# MODULE_FPGA.net
KiCad netlist of a schematic drawn in Altium Designer
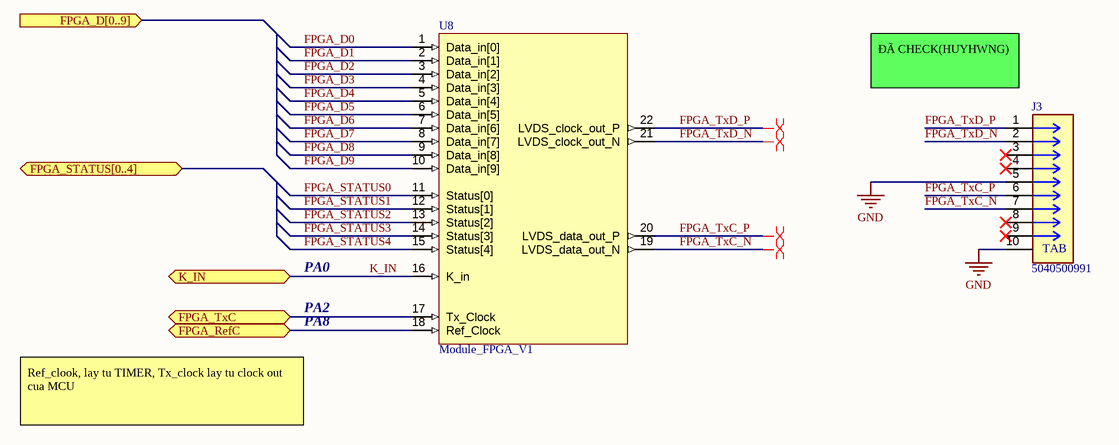
[diagram p0: MODULE_FPGA.SchDoc]

(export (version "E")
  (design (tool "Eeschema 10.0.6"))
  (components
    (comp (ref "J3")
      (value "5040500991")
      (footprint "5040500991")
      (description "Connector Header Surface Mount, Right Angle 9 position 0.059\" (1.50mm)")
      (libsource (lib "COMM_SCHLIB") (part "5040500991"))
    )
    (comp (ref "U8")
      (value "Module_FPGA_V1")
      (footprint "MODULE_FPGA")
      (libsource (lib "3_HuyHung") (part "Module_FPGA_V1"))
    )
  )
  (nets
    (net (code "1") (name "/FPGA_D0") (class "Default")
      (node (ref "U8") (pin "1") (pinfunction "Data_in[0]_1") (pintype "input"))
    )
    (net (code "2") (name "/FPGA_D1") (class "Default")
      (node (ref "U8") (pin "2") (pinfunction "Data_in[1]_2") (pintype "input"))
    )
    (net (code "3") (name "/FPGA_D2") (class "Default")
      (node (ref "U8") (pin "3") (pinfunction "Data_in[2]_3") (pintype "input"))
    )
    (net (code "4") (name "/FPGA_D3") (class "Default")
      (node (ref "U8") (pin "4") (pinfunction "Data_in[3]_4") (pintype "input"))
    )
    (net (code "5") (name "/FPGA_D4") (class "Default")
      (node (ref "U8") (pin "5") (pinfunction "Data_in[4]_5") (pintype "input"))
    )
    (net (code "6") (name "/FPGA_D5") (class "Default")
      (node (ref "U8") (pin "6") (pinfunction "Data_in[5]_6") (pintype "input"))
    )
    (net (code "7") (name "/FPGA_D6") (class "Default")
      (node (ref "U8") (pin "7") (pinfunction "Data_in[6]_7") (pintype "input"))
    )
    (net (code "8") (name "/FPGA_D7") (class "Default")
      (node (ref "U8") (pin "8") (pinfunction "Data_in[7]_8") (pintype "input"))
    )
    (net (code "9") (name "/FPGA_D8") (class "Default")
      (node (ref "U8") (pin "9") (pinfunction "Data_in[8]_9") (pintype "input"))
    )
    (net (code "10") (name "/FPGA_D9") (class "Default")
      (node (ref "U8") (pin "10") (pinfunction "Data_in[9]_10") (pintype "input"))
    )
    (net (code "12") (name "/FPGA_RefC") (class "Default")
      (node (ref "U8") (pin "18") (pinfunction "Ref_Clock_18") (pintype "input"))
    )
    (net (code "13") (name "/FPGA_STATUS0") (class "Default")
      (node (ref "U8") (pin "11") (pinfunction "Status[0]_11") (pintype "input"))
    )
    (net (code "14") (name "/FPGA_STATUS1") (class "Default")
      (node (ref "U8") (pin "12") (pinfunction "Status[1]_12") (pintype "input"))
    )
    (net (code "15") (name "/FPGA_STATUS2") (class "Default")
      (node (ref "U8") (pin "13") (pinfunction "Status[2]_13") (pintype "input"))
    )
    (net (code "16") (name "/FPGA_STATUS3") (class "Default")
      (node (ref "U8") (pin "14") (pinfunction "Status[3]_14") (pintype "input"))
    )
    (net (code "17") (name "/FPGA_STATUS4") (class "Default")
      (node (ref "U8") (pin "15") (pinfunction "Status[4]_15") (pintype "input"))
    )
    (net (code "19") (name "/FPGA_TxC") (class "Default")
      (node (ref "U8") (pin "17") (pinfunction "Tx_Clock_17") (pintype "input"))
    )
    (net (code "20") (name "/FPGA_TxC_N") (class "Default")
      (node (ref "J3") (pin "7") (pinfunction "7_7") (pintype "passive"))
      (node (ref "U8") (pin "19") (pinfunction "LVDS_data_out_N_19") (pintype "output"))
    )
    (net (code "21") (name "/FPGA_TxC_P") (class "Default")
      (node (ref "J3") (pin "6") (pinfunction "6_6") (pintype "passive"))
      (node (ref "U8") (pin "20") (pinfunction "LVDS_data_out_P_20") (pintype "output"))
    )
    (net (code "22") (name "/FPGA_TxD_N") (class "Default")
      (node (ref "J3") (pin "2") (pinfunction "2_2") (pintype "passive"))
      (node (ref "U8") (pin "21") (pinfunction "LVDS_clock_out_N_21") (pintype "output"))
    )
    (net (code "23") (name "/FPGA_TxD_P") (class "Default")
      (node (ref "J3") (pin "1") (pinfunction "1_1") (pintype "passive"))
      (node (ref "U8") (pin "22") (pinfunction "LVDS_clock_out_P_22") (pintype "output"))
    )
    (net (code "24") (name "/K_IN") (class "Default")
      (node (ref "U8") (pin "16") (pinfunction "K_in_16") (pintype "input"))
    )
    (net (code "25") (name "GND") (class "Default")
      (node (ref "J3") (pin "10") (pinfunction "10_10") (pintype "passive"))
      (node (ref "J3") (pin "5") (pinfunction "5_5") (pintype "passive"))
    )
    (net (code "26") (name "unconnected-(J3-Pad3)") (class "Default")
      (node (ref "J3") (pin "3") (pinfunction "3_3") (pintype "passive+no_connect"))
    )
    (net (code "27") (name "unconnected-(J3-Pad4)") (class "Default")
      (node (ref "J3") (pin "4") (pinfunction "4_4") (pintype "passive+no_connect"))
    )
    (net (code "28") (name "unconnected-(J3-Pad8)") (class "Default")
      (node (ref "J3") (pin "8") (pinfunction "8_8") (pintype "passive+no_connect"))
    )
    (net (code "29") (name "unconnected-(J3-Pad9)") (class "Default")
      (node (ref "J3") (pin "9") (pinfunction "9_9") (pintype "passive+no_connect"))
    )
  )
)
